# TK518_P18V-PSU.net
KiCad netlist of a schematic drawn in Altium Designer
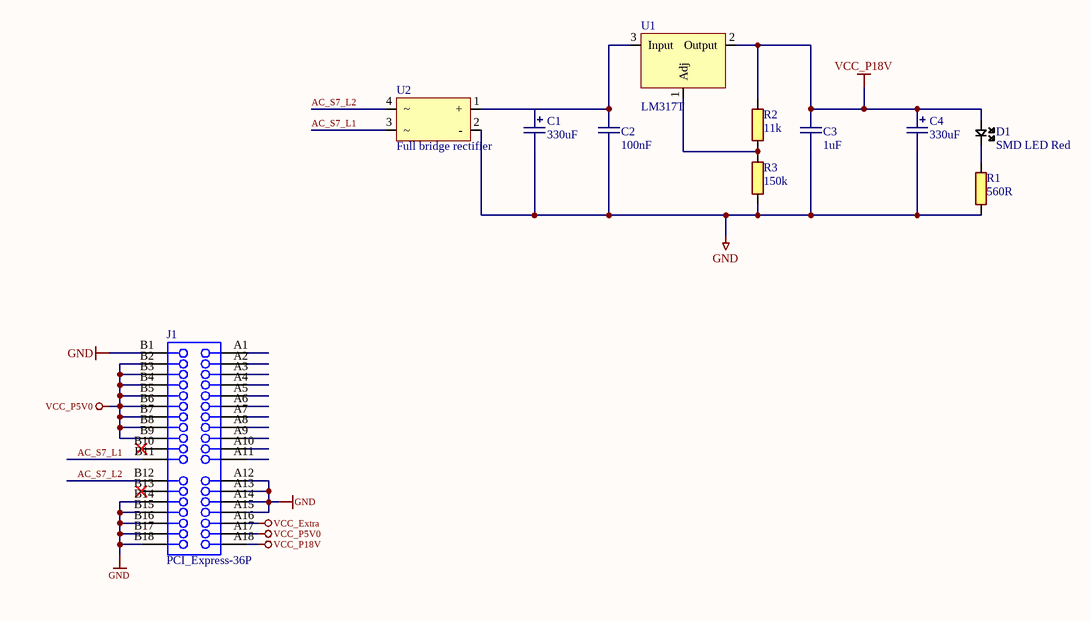
[diagram p0: TK518_P18V-PSU.SchDoc]

(export (version "E")
  (design (tool "Eeschema 10.0.6"))
  (components
    (comp (ref "C1")
      (value "330uF")
      (footprint "CAPPR35D08H16")
      (description "25V elektrolytt")
      (libsource (lib "OVLib") (part "POLCAP"))
    )
    (comp (ref "C2")
      (value "100nF")
      (footprint "CAPC0603(1608)55_N")
      (description "X7R 50V 5%")
      (libsource (lib "OVLib") (part "CAP"))
    )
    (comp (ref "C3")
      (value "1uF")
      (footprint "CAPC0805(2012)100_N")
      (description "X7R 50V 10%")
      (libsource (lib "OVLib") (part "CAP"))
    )
    (comp (ref "C4")
      (value "330uF")
      (footprint "CAPPR35D08H16")
      (description "25V elektrolytt")
      (libsource (lib "OVLib") (part "POLCAP"))
    )
    (comp (ref "D1")
      (value "SMD LED Red")
      (footprint "I_LEDC0603(1608)_N")
      (libsource (lib "OVLib") (part "LED"))
    )
    (comp (ref "J1")
      (value "PCI_Express-36P")
      (footprint "PCIeX1-GF-2D-1000-1K-O36")
      (description "PCI express PCB kortkankonnektor")
      (libsource (lib "OVLib") (part "PCI_Express-36P"))
    )
    (comp (ref "R1")
      (value "560R")
      (footprint "RESC0603(1608)_N")
      (description "0.1W 1% Thick film resistor")
      (libsource (lib "OVLib") (part "Resistor2"))
    )
    (comp (ref "R2")
      (value "11k")
      (footprint "RESC0603(1608)_N")
      (description "0.1W 1% Thick film resistor")
      (libsource (lib "OVLib") (part "Resistor2"))
    )
    (comp (ref "R3")
      (value "150k")
      (footprint "RESC0603(1608)_N")
      (description "0.1W 1% Thick film resistor")
      (libsource (lib "OVLib") (part "Resistor2"))
    )
    (comp (ref "U1")
      (value "LM317T")
      (footprint "TO-220-3P")
      (description "Adjustable Regulator")
      (libsource (lib "LM317T Adjustable Regulator") (part "LM317T"))
    )
    (comp (ref "U2")
      (value "Full bridge rectifier")
      (footprint "SOP500P1010X260-4N")
      (libsource (lib "DBLS207G Rectifier") (part "DBLS07G Rectifier"))
    )
  )
  (nets
    (net (code "1") (name "/AC_S7_L1") (class "Default")
      (node (ref "J1") (pin "B11") (pinfunction "B11_B11") (pintype "passive"))
      (node (ref "U2") (pin "3") (pinfunction "~_3") (pintype "passive"))
    )
    (net (code "2") (name "/AC_S7_L2") (class "Default")
      (node (ref "J1") (pin "B12") (pinfunction "B12_B12") (pintype "passive"))
      (node (ref "U2") (pin "4") (pinfunction "~_4") (pintype "passive"))
    )
    (net (code "3") (name "GND") (class "Default")
      (node (ref "C1") (pin "1") (pinfunction "1_1") (pintype "passive"))
      (node (ref "C2") (pin "1") (pinfunction "1_1") (pintype "passive"))
      (node (ref "C3") (pin "1") (pinfunction "1_1") (pintype "passive"))
      (node (ref "C4") (pin "1") (pinfunction "1_1") (pintype "passive"))
      (node (ref "J1") (pin "A12") (pinfunction "A12_A12") (pintype "passive"))
      (node (ref "J1") (pin "A13") (pinfunction "A13_A13") (pintype "passive"))
      (node (ref "J1") (pin "A14") (pinfunction "A14_A14") (pintype "passive"))
      (node (ref "J1") (pin "A15") (pinfunction "A15_A15") (pintype "passive"))
      (node (ref "J1") (pin "B1") (pinfunction "B1_B1") (pintype "passive"))
      (node (ref "J1") (pin "B14") (pinfunction "B14_B14") (pintype "passive"))
      (node (ref "J1") (pin "B15") (pinfunction "B15_B15") (pintype "passive"))
      (node (ref "J1") (pin "B16") (pinfunction "B16_B16") (pintype "passive"))
      (node (ref "J1") (pin "B17") (pinfunction "B17_B17") (pintype "passive"))
      (node (ref "J1") (pin "B18") (pinfunction "B18_B18") (pintype "passive"))
      (node (ref "R1") (pin "1") (pinfunction "1_1") (pintype "passive"))
      (node (ref "R3") (pin "1") (pinfunction "1_1") (pintype "passive"))
      (node (ref "U2") (pin "2") (pinfunction "-_2") (pintype "passive"))
    )
    (net (code "4") (name "Net-(D1-Pad2)") (class "Default")
      (node (ref "D1") (pin "2") (pinfunction "2_2") (pintype "passive"))
      (node (ref "R1") (pin "2") (pinfunction "2_2") (pintype "passive"))
    )
    (net (code "5") (name "Net-(U1-Adj)") (class "Default")
      (node (ref "R2") (pin "1") (pinfunction "1_1") (pintype "passive"))
      (node (ref "R3") (pin "2") (pinfunction "2_2") (pintype "passive"))
      (node (ref "U1") (pin "1") (pinfunction "Adj_1") (pintype "passive"))
    )
    (net (code "6") (name "Net-(U1-Input)") (class "Default")
      (node (ref "C1") (pin "2") (pinfunction "2_2") (pintype "passive"))
      (node (ref "C2") (pin "2") (pinfunction "2_2") (pintype "passive"))
      (node (ref "U1") (pin "3") (pinfunction "Input_3") (pintype "passive"))
      (node (ref "U2") (pin "1") (pinfunction "+_1") (pintype "passive"))
    )
    (net (code "7") (name "VCC_Extra") (class "Default")
      (node (ref "J1") (pin "A16") (pinfunction "A16_A16") (pintype "passive"))
    )
    (net (code "8") (name "VCC_P5V0") (class "Default")
      (node (ref "J1") (pin "A17") (pinfunction "A17_A17") (pintype "passive"))
      (node (ref "J1") (pin "B2") (pinfunction "B2_B2") (pintype "passive"))
      (node (ref "J1") (pin "B3") (pinfunction "B3_B3") (pintype "passive"))
      (node (ref "J1") (pin "B4") (pinfunction "B4_B4") (pintype "passive"))
      (node (ref "J1") (pin "B5") (pinfunction "B5_B5") (pintype "passive"))
      (node (ref "J1") (pin "B6") (pinfunction "B6_B6") (pintype "passive"))
      (node (ref "J1") (pin "B7") (pinfunction "B7_B7") (pintype "passive"))
      (node (ref "J1") (pin "B8") (pinfunction "B8_B8") (pintype "passive"))
      (node (ref "J1") (pin "B9") (pinfunction "B9_B9") (pintype "passive"))
    )
    (net (code "9") (name "VCC_P18V") (class "Default")
      (node (ref "C3") (pin "2") (pinfunction "2_2") (pintype "passive"))
      (node (ref "C4") (pin "2") (pinfunction "2_2") (pintype "passive"))
      (node (ref "D1") (pin "1") (pinfunction "1_1") (pintype "passive"))
      (node (ref "J1") (pin "A18") (pinfunction "A18_A18") (pintype "passive"))
      (node (ref "R2") (pin "2") (pinfunction "2_2") (pintype "passive"))
      (node (ref "U1") (pin "2") (pinfunction "Output_2") (pintype "passive"))
    )
    (net (code "10") (name "unconnected-(J1-PadA1)") (class "Default")
      (node (ref "J1") (pin "A1") (pinfunction "A1_A1") (pintype "passive"))
    )
    (net (code "11") (name "unconnected-(J1-PadA2)") (class "Default")
      (node (ref "J1") (pin "A2") (pinfunction "A2_A2") (pintype "passive"))
    )
    (net (code "12") (name "unconnected-(J1-PadA3)") (class "Default")
      (node (ref "J1") (pin "A3") (pinfunction "A3_A3") (pintype "passive"))
    )
    (net (code "13") (name "unconnected-(J1-PadA4)") (class "Default")
      (node (ref "J1") (pin "A4") (pinfunction "A4_A4") (pintype "passive"))
    )
    (net (code "14") (name "unconnected-(J1-PadA5)") (class "Default")
      (node (ref "J1") (pin "A5") (pinfunction "A5_A5") (pintype "passive"))
    )
    (net (code "15") (name "unconnected-(J1-PadA6)") (class "Default")
      (node (ref "J1") (pin "A6") (pinfunction "A6_A6") (pintype "passive"))
    )
    (net (code "16") (name "unconnected-(J1-PadA7)") (class "Default")
      (node (ref "J1") (pin "A7") (pinfunction "A7_A7") (pintype "passive"))
    )
    (net (code "17") (name "unconnected-(J1-PadA8)") (class "Default")
      (node (ref "J1") (pin "A8") (pinfunction "A8_A8") (pintype "passive"))
    )
    (net (code "18") (name "unconnected-(J1-PadA9)") (class "Default")
      (node (ref "J1") (pin "A9") (pinfunction "A9_A9") (pintype "passive"))
    )
    (net (code "19") (name "unconnected-(J1-PadA10)") (class "Default")
      (node (ref "J1") (pin "A10") (pinfunction "A10_A10") (pintype "passive"))
    )
    (net (code "20") (name "unconnected-(J1-PadA11)") (class "Default")
      (node (ref "J1") (pin "A11") (pinfunction "A11_A11") (pintype "passive"))
    )
    (net (code "21") (name "unconnected-(J1-PadB10)") (class "Default")
      (node (ref "J1") (pin "B10") (pinfunction "B10_B10") (pintype "passive+no_connect"))
    )
    (net (code "22") (name "unconnected-(J1-PadB13)") (class "Default")
      (node (ref "J1") (pin "B13") (pinfunction "B13_B13") (pintype "passive+no_connect"))
    )
  )
)
